# ProcessorTestBoardV1_0.net
KiCad netlist of a schematic drawn in EAGLE
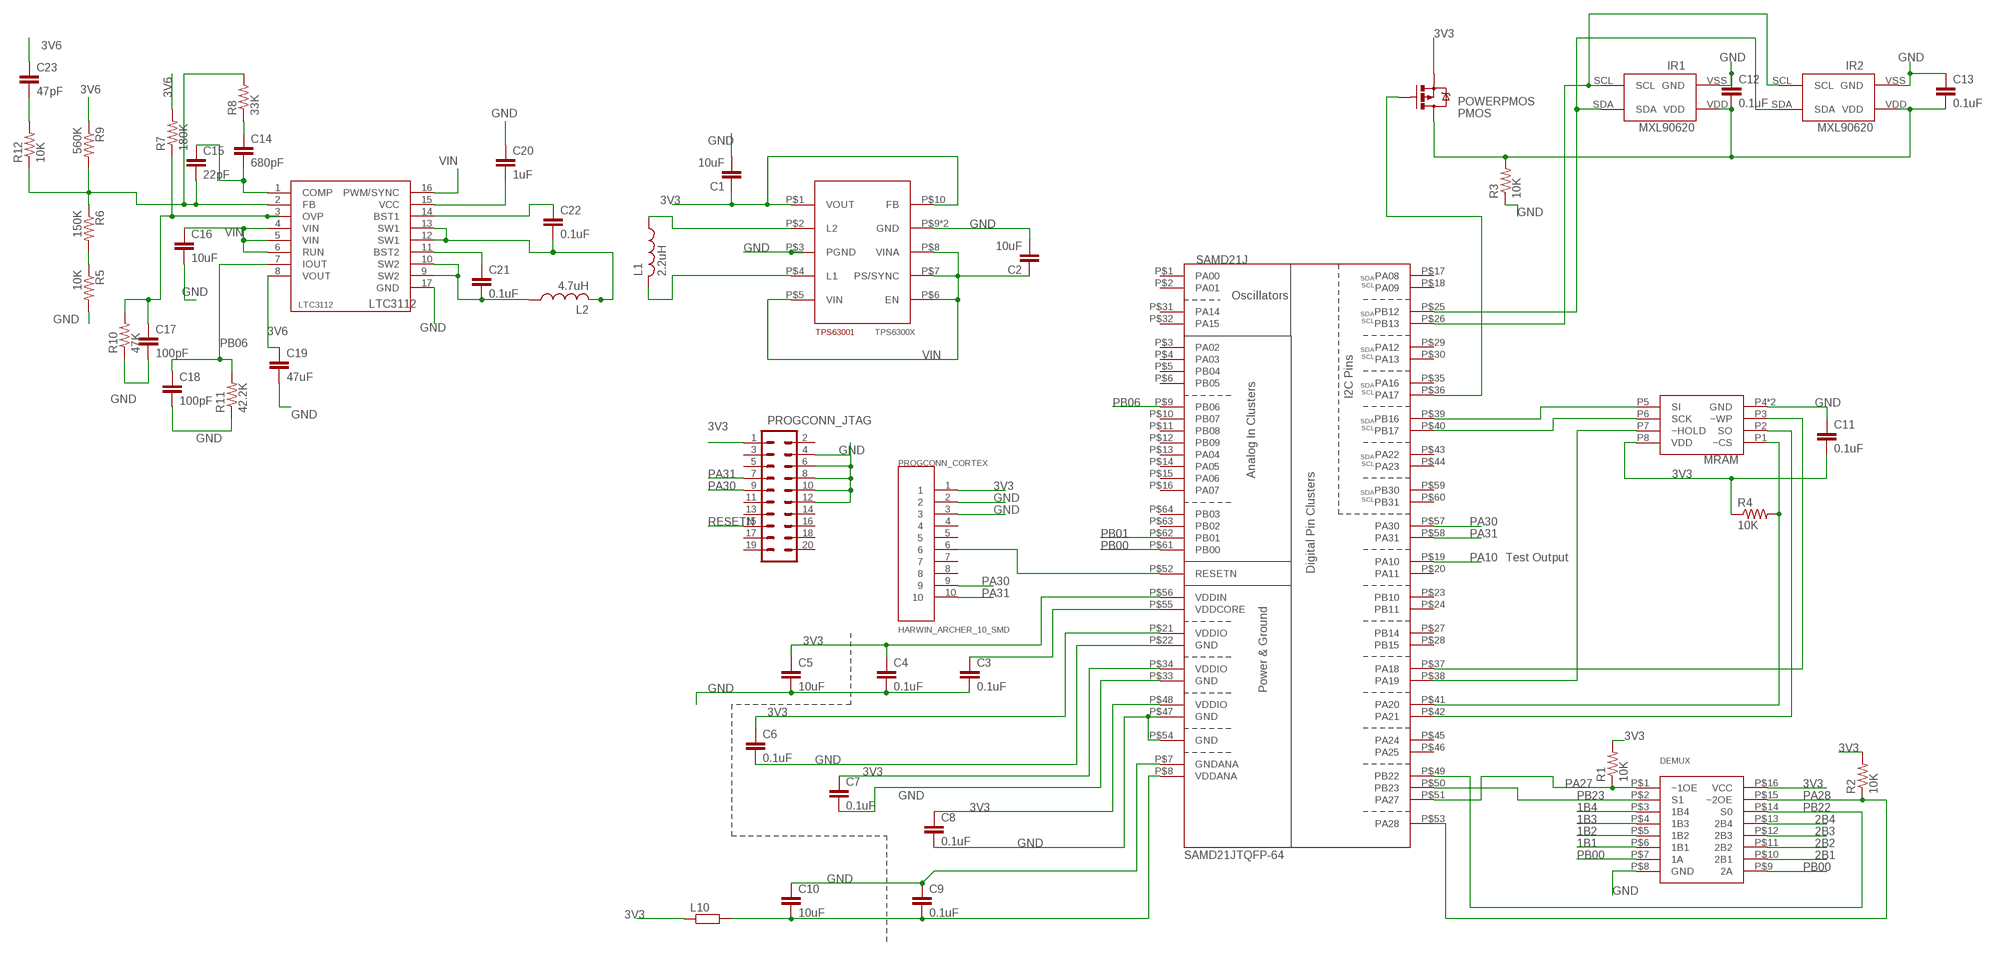
[diagram p0: schematic, sheet 1]

(export (version "E")
  (design (tool "Eeschema 10.0.6"))
  (components
    (comp (ref "C1")
      (value "10uF")
      (footprint "eagle-import:0805")
      (libsource (lib "eagle-import") (part "CAP0805"))
    )
    (comp (ref "C2")
      (value "10uF")
      (footprint "eagle-import:0805")
      (libsource (lib "eagle-import") (part "CAP0805"))
    )
    (comp (ref "C3")
      (value "0.1uF")
      (footprint "eagle-import:0805")
      (libsource (lib "eagle-import") (part "CAP0805"))
    )
    (comp (ref "C4")
      (value "0.1uF")
      (footprint "eagle-import:0805")
      (libsource (lib "eagle-import") (part "CAP0805"))
    )
    (comp (ref "C5")
      (value "10uF")
      (footprint "eagle-import:0805")
      (libsource (lib "eagle-import") (part "CAP0805"))
    )
    (comp (ref "C6")
      (value "0.1uF")
      (footprint "eagle-import:0805")
      (libsource (lib "eagle-import") (part "CAP0805"))
    )
    (comp (ref "C7")
      (value "0.1uF")
      (footprint "eagle-import:0805")
      (libsource (lib "eagle-import") (part "CAP0805"))
    )
    (comp (ref "C8")
      (value "0.1uF")
      (footprint "eagle-import:0805")
      (libsource (lib "eagle-import") (part "CAP0805"))
    )
    (comp (ref "C9")
      (value "0.1uF")
      (footprint "eagle-import:0805")
      (libsource (lib "eagle-import") (part "CAP0805"))
    )
    (comp (ref "C10")
      (value "10uF")
      (footprint "eagle-import:0805")
      (libsource (lib "eagle-import") (part "CAP0805"))
    )
    (comp (ref "C11")
      (value "0.1uF")
      (footprint "eagle-import:0805")
      (libsource (lib "eagle-import") (part "CAP0805"))
    )
    (comp (ref "C12")
      (value "0.1uF")
      (footprint "eagle-import:0805")
      (libsource (lib "eagle-import") (part "CAP0805"))
    )
    (comp (ref "C13")
      (value "0.1uF")
      (footprint "eagle-import:0805")
      (libsource (lib "eagle-import") (part "CAP0805"))
    )
    (comp (ref "C14")
      (value "680pF")
      (footprint "eagle-import:0805")
      (libsource (lib "eagle-import") (part "CAP0805"))
    )
    (comp (ref "C15")
      (value "22pF")
      (footprint "eagle-import:0805")
      (libsource (lib "eagle-import") (part "CAP0805"))
    )
    (comp (ref "C16")
      (value "10uF")
      (footprint "eagle-import:0805")
      (libsource (lib "eagle-import") (part "CAP0805"))
    )
    (comp (ref "C17")
      (value "100pF")
      (footprint "eagle-import:0805")
      (libsource (lib "eagle-import") (part "CAP0805"))
    )
    (comp (ref "C18")
      (value "100pF")
      (footprint "eagle-import:0805")
      (libsource (lib "eagle-import") (part "CAP0805"))
    )
    (comp (ref "C19")
      (value "47uF")
      (footprint "eagle-import:0805")
      (libsource (lib "eagle-import") (part "CAP0805"))
    )
    (comp (ref "C20")
      (value "1uF")
      (footprint "eagle-import:0805")
      (libsource (lib "eagle-import") (part "CAP0805"))
    )
    (comp (ref "C21")
      (value "0.1uF")
      (footprint "eagle-import:0805")
      (libsource (lib "eagle-import") (part "CAP0805"))
    )
    (comp (ref "C22")
      (value "0.1uF")
      (footprint "eagle-import:0805")
      (libsource (lib "eagle-import") (part "CAP0805"))
    )
    (comp (ref "C23")
      (value "47pF")
      (footprint "eagle-import:0805")
      (libsource (lib "eagle-import") (part "CAP0805"))
    )
    (comp (ref "DEMUX")
      (value "SN74CBTLV3253")
      (footprint "eagle-import:SOIC16R")
      (libsource (lib "eagle-import") (part "SN74CBTLV3253"))
    )
    (comp (ref "IR1")
      (value "MXL90620")
      (footprint "eagle-import:MXL90620")
      (libsource (lib "eagle-import") (part "MXL90620"))
    )
    (comp (ref "IR2")
      (value "MXL90620")
      (footprint "eagle-import:MXL90620")
      (libsource (lib "eagle-import") (part "MXL90620"))
    )
    (comp (ref "L1")
      (value "2.2uH")
      (footprint "eagle-import:L3225M")
      (libsource (lib "eagle-import") (part "L-USL3225M"))
    )
    (comp (ref "L2")
      (value "4.7uH")
      (footprint "eagle-import:L3225M")
      (libsource (lib "eagle-import") (part "L-USL3225M"))
    )
    (comp (ref "L10")
      (value "R-EU_R0805")
      (footprint "eagle-import:R0805")
      (libsource (lib "eagle-import") (part "R-EU_R0805"))
    )
    (comp (ref "LTC3112")
      (value "LTC3112")
      (footprint "eagle-import:DHD16")
      (libsource (lib "eagle-import") (part "LTC3112"))
    )
    (comp (ref "MRAM")
      (value "MR25H10CDC")
      (footprint "eagle-import:8PXMO-229")
      (libsource (lib "eagle-import") (part "MR25H10CDC"))
    )
    (comp (ref "PMOS")
      (value "POWERPMOS")
      (footprint "eagle-import:SO08")
      (libsource (lib "eagle-import") (part "POWERPMOS"))
    )
    (comp (ref "PROGCONN_CORTEX")
      (value "HARWIN_ARCHER_10_SMD")
      (footprint "eagle-import:HARWIN_ARCHER_10_SMD")
      (libsource (lib "eagle-import") (part "HARWIN_ARCHER_10_SMD"))
    )
    (comp (ref "PROGCONN_JTAG")
      (value "IDC_JTAG_CONNECTOR")
      (footprint "eagle-import:2X10")
      (libsource (lib "eagle-import") (part "IDC_JTAG_CONNECTOR"))
    )
    (comp (ref "R1")
      (value "10K")
      (footprint "eagle-import:0805")
      (libsource (lib "eagle-import") (part "RESISTOR"))
    )
    (comp (ref "R2")
      (value "10K")
      (footprint "eagle-import:0805")
      (libsource (lib "eagle-import") (part "RESISTOR"))
    )
    (comp (ref "R3")
      (value "10K")
      (footprint "eagle-import:0805")
      (libsource (lib "eagle-import") (part "RESISTOR"))
    )
    (comp (ref "R4")
      (value "10K")
      (footprint "eagle-import:0805")
      (libsource (lib "eagle-import") (part "RESISTOR"))
    )
    (comp (ref "R5")
      (value "10K")
      (footprint "eagle-import:0805")
      (libsource (lib "eagle-import") (part "RESISTOR"))
    )
    (comp (ref "R6")
      (value "150K")
      (footprint "eagle-import:0805")
      (libsource (lib "eagle-import") (part "RESISTOR"))
    )
    (comp (ref "R7")
      (value "180K")
      (footprint "eagle-import:0805")
      (libsource (lib "eagle-import") (part "RESISTOR"))
    )
    (comp (ref "R8")
      (value "33K")
      (footprint "eagle-import:0805")
      (libsource (lib "eagle-import") (part "RESISTOR"))
    )
    (comp (ref "R9")
      (value "560K")
      (footprint "eagle-import:0805")
      (libsource (lib "eagle-import") (part "RESISTOR"))
    )
    (comp (ref "R10")
      (value "47K")
      (footprint "eagle-import:0805")
      (libsource (lib "eagle-import") (part "RESISTOR"))
    )
    (comp (ref "R11")
      (value "42.2K")
      (footprint "eagle-import:0805")
      (libsource (lib "eagle-import") (part "RESISTOR"))
    )
    (comp (ref "R12")
      (value "10K")
      (footprint "eagle-import:0805")
      (libsource (lib "eagle-import") (part "RESISTOR"))
    )
    (comp (ref "SAMD21J")
      (value "SAMD21JTQFP-64")
      (footprint "eagle-import:TQFP-64")
      (libsource (lib "eagle-import") (part "SAMD21JTQFP-64"))
    )
    (comp (ref "TPS63001")
      (value "TPS6300X")
      (footprint "eagle-import:QFN10_POWERPAD")
      (libsource (lib "eagle-import") (part "TPS6300X"))
    )
  )
  (nets
    (net (code "1") (name "/1B1") (class "Default")
      (node (ref "DEMUX") (pin "P$6") (pinfunction "1B1_P$6") (pintype "bidirectional"))
    )
    (net (code "2") (name "/1B2") (class "Default")
      (node (ref "DEMUX") (pin "P$5") (pinfunction "1B2_P$5") (pintype "bidirectional"))
    )
    (net (code "3") (name "/1B3") (class "Default")
      (node (ref "DEMUX") (pin "P$4") (pinfunction "1B3_P$4") (pintype "bidirectional"))
    )
    (net (code "4") (name "/1B4") (class "Default")
      (node (ref "DEMUX") (pin "P$3") (pinfunction "1B4_P$3") (pintype "bidirectional"))
    )
    (net (code "5") (name "/2B1") (class "Default")
      (node (ref "DEMUX") (pin "P$10") (pinfunction "2B1_P$10") (pintype "bidirectional"))
    )
    (net (code "6") (name "/2B2") (class "Default")
      (node (ref "DEMUX") (pin "P$11") (pinfunction "2B2_P$11") (pintype "bidirectional"))
    )
    (net (code "7") (name "/2B3") (class "Default")
      (node (ref "DEMUX") (pin "P$12") (pinfunction "2B3_P$12") (pintype "bidirectional"))
    )
    (net (code "8") (name "/2B4") (class "Default")
      (node (ref "DEMUX") (pin "P$13") (pinfunction "2B4_P$13") (pintype "bidirectional"))
    )
    (net (code "9") (name "/3V3") (class "Default")
      (node (ref "C1") (pin "1") (pinfunction "1_1") (pintype "passive"))
      (node (ref "C11") (pin "2") (pinfunction "2_2") (pintype "passive"))
      (node (ref "C4") (pin "1") (pinfunction "1_1") (pintype "passive"))
      (node (ref "C5") (pin "1") (pinfunction "1_1") (pintype "passive"))
      (node (ref "C6") (pin "1") (pinfunction "1_1") (pintype "passive"))
      (node (ref "C7") (pin "1") (pinfunction "1_1") (pintype "passive"))
      (node (ref "C8") (pin "1") (pinfunction "1_1") (pintype "passive"))
      (node (ref "DEMUX") (pin "P$16") (pinfunction "VCC_P$16") (pintype "bidirectional"))
      (node (ref "L10") (pin "1") (pinfunction "1_1") (pintype "passive"))
      (node (ref "MRAM") (pin "P8") (pinfunction "VDD_P8") (pintype "bidirectional"))
      (node (ref "PMOS") (pin "1") (pinfunction "S_1") (pintype "passive"))
      (node (ref "PMOS") (pin "2") (pinfunction "S_2") (pintype "passive"))
      (node (ref "PMOS") (pin "3") (pinfunction "S_3") (pintype "passive"))
      (node (ref "PROGCONN_CORTEX") (pin "1") (pinfunction "1_1") (pintype "bidirectional"))
      (node (ref "PROGCONN_JTAG") (pin "1") (pinfunction "1_1") (pintype "passive"))
      (node (ref "R1") (pin "2") (pinfunction "2_2") (pintype "passive"))
      (node (ref "R2") (pin "2") (pinfunction "2_2") (pintype "passive"))
      (node (ref "R4") (pin "1") (pinfunction "1_1") (pintype "passive"))
      (node (ref "SAMD21J") (pin "P$21") (pinfunction "VDDIO_P$21") (pintype "power_in"))
      (node (ref "SAMD21J") (pin "P$34") (pinfunction "VDDIO_P$34") (pintype "power_in"))
      (node (ref "SAMD21J") (pin "P$48") (pinfunction "VDDIO_P$48") (pintype "power_in"))
      (node (ref "SAMD21J") (pin "P$56") (pinfunction "VDDIN_P$56") (pintype "power_in"))
      (node (ref "TPS63001") (pin "P$1") (pinfunction "VOUT_P$1") (pintype "output"))
      (node (ref "TPS63001") (pin "P$10") (pinfunction "FB_P$10") (pintype "input"))
    )
    (net (code "10") (name "/3V6") (class "Default")
      (node (ref "C19") (pin "1") (pinfunction "1_1") (pintype "passive"))
      (node (ref "C23") (pin "1") (pinfunction "1_1") (pintype "passive"))
      (node (ref "LTC3112") (pin "8") (pinfunction "VOUT_8") (pintype "bidirectional"))
      (node (ref "R7") (pin "2") (pinfunction "2_2") (pintype "passive"))
      (node (ref "R9") (pin "1") (pinfunction "1_1") (pintype "passive"))
    )
    (net (code "11") (name "/GND") (class "Default")
      (node (ref "C1") (pin "2") (pinfunction "2_2") (pintype "passive"))
      (node (ref "C10") (pin "1") (pinfunction "1_1") (pintype "passive"))
      (node (ref "C11") (pin "1") (pinfunction "1_1") (pintype "passive"))
      (node (ref "C12") (pin "1") (pinfunction "1_1") (pintype "passive"))
      (node (ref "C13") (pin "1") (pinfunction "1_1") (pintype "passive"))
      (node (ref "C16") (pin "2") (pinfunction "2_2") (pintype "passive"))
      (node (ref "C17") (pin "2") (pinfunction "2_2") (pintype "passive"))
      (node (ref "C18") (pin "2") (pinfunction "2_2") (pintype "passive"))
      (node (ref "C19") (pin "2") (pinfunction "2_2") (pintype "passive"))
      (node (ref "C2") (pin "2") (pinfunction "2_2") (pintype "passive"))
      (node (ref "C20") (pin "1") (pinfunction "1_1") (pintype "passive"))
      (node (ref "C3") (pin "2") (pinfunction "2_2") (pintype "passive"))
      (node (ref "C4") (pin "2") (pinfunction "2_2") (pintype "passive"))
      (node (ref "C5") (pin "2") (pinfunction "2_2") (pintype "passive"))
      (node (ref "C6") (pin "2") (pinfunction "2_2") (pintype "passive"))
      (node (ref "C7") (pin "2") (pinfunction "2_2") (pintype "passive"))
      (node (ref "C8") (pin "2") (pinfunction "2_2") (pintype "passive"))
      (node (ref "C9") (pin "1") (pinfunction "1_1") (pintype "passive"))
      (node (ref "DEMUX") (pin "P$8") (pinfunction "GND_P$8") (pintype "bidirectional"))
      (node (ref "IR1") (pin "VSS") (pinfunction "GND_VSS") (pintype "bidirectional"))
      (node (ref "IR2") (pin "VSS") (pinfunction "GND_VSS") (pintype "bidirectional"))
      (node (ref "LTC3112") (pin "17") (pinfunction "GND_17") (pintype "bidirectional"))
      (node (ref "MRAM") (pin "P4") (pinfunction "GND_P4") (pintype "bidirectional"))
      (node (ref "MRAM") (pin "P9") (pinfunction "GND_P9") (pintype "bidirectional"))
      (node (ref "PROGCONN_CORTEX") (pin "2") (pinfunction "2_2") (pintype "bidirectional"))
      (node (ref "PROGCONN_CORTEX") (pin "3") (pinfunction "3_3") (pintype "bidirectional"))
      (node (ref "PROGCONN_JTAG") (pin "10") (pinfunction "10_10") (pintype "passive"))
      (node (ref "PROGCONN_JTAG") (pin "12") (pinfunction "12_12") (pintype "passive"))
      (node (ref "PROGCONN_JTAG") (pin "4") (pinfunction "4_4") (pintype "passive"))
      (node (ref "PROGCONN_JTAG") (pin "6") (pinfunction "6_6") (pintype "passive"))
      (node (ref "PROGCONN_JTAG") (pin "8") (pinfunction "8_8") (pintype "passive"))
      (node (ref "R10") (pin "1") (pinfunction "1_1") (pintype "passive"))
      (node (ref "R11") (pin "1") (pinfunction "1_1") (pintype "passive"))
      (node (ref "R3") (pin "1") (pinfunction "1_1") (pintype "passive"))
      (node (ref "R5") (pin "2") (pinfunction "2_2") (pintype "passive"))
      (node (ref "SAMD21J") (pin "P$22") (pinfunction "GND_P$22") (pintype "power_in"))
      (node (ref "SAMD21J") (pin "P$33") (pinfunction "GND_P$33") (pintype "power_in"))
      (node (ref "SAMD21J") (pin "P$47") (pinfunction "GND_P$47") (pintype "power_in"))
      (node (ref "SAMD21J") (pin "P$54") (pinfunction "GND_P$54") (pintype "power_in"))
      (node (ref "SAMD21J") (pin "P$7") (pinfunction "GNDANA_P$7") (pintype "power_in"))
      (node (ref "TPS63001") (pin "P$3") (pinfunction "PGND_P$3") (pintype "input"))
      (node (ref "TPS63001") (pin "P$9") (pinfunction "GND_P$9") (pintype "input"))
      (node (ref "TPS63001") (pin "PAD") (pinfunction "GND_PAD") (pintype "input"))
    )
    (net (code "12") (name "/PA10") (class "Default")
      (node (ref "SAMD21J") (pin "P$19") (pinfunction "PA10_P$19") (pintype "bidirectional"))
    )
    (net (code "13") (name "/PA27") (class "Default")
      (node (ref "DEMUX") (pin "P$1") (pinfunction "~{1OE}_P$1") (pintype "bidirectional"))
      (node (ref "R1") (pin "1") (pinfunction "1_1") (pintype "passive"))
      (node (ref "SAMD21J") (pin "P$51") (pinfunction "PA27_P$51") (pintype "bidirectional"))
    )
    (net (code "14") (name "/PA28") (class "Default")
      (node (ref "DEMUX") (pin "P$15") (pinfunction "~{2OE}_P$15") (pintype "bidirectional"))
      (node (ref "R2") (pin "1") (pinfunction "1_1") (pintype "passive"))
      (node (ref "SAMD21J") (pin "P$53") (pinfunction "PA28_P$53") (pintype "bidirectional"))
    )
    (net (code "15") (name "/PA30") (class "Default")
      (node (ref "PROGCONN_CORTEX") (pin "9") (pinfunction "9_9") (pintype "bidirectional"))
      (node (ref "PROGCONN_JTAG") (pin "9") (pinfunction "9_9") (pintype "passive"))
      (node (ref "SAMD21J") (pin "P$57") (pinfunction "PA30_P$57") (pintype "bidirectional"))
    )
    (net (code "16") (name "/PA31") (class "Default")
      (node (ref "PROGCONN_CORTEX") (pin "10") (pinfunction "10_10") (pintype "bidirectional"))
      (node (ref "PROGCONN_JTAG") (pin "7") (pinfunction "7_7") (pintype "passive"))
      (node (ref "SAMD21J") (pin "P$58") (pinfunction "PA31_P$58") (pintype "bidirectional"))
    )
    (net (code "17") (name "/PB00") (class "Default")
      (node (ref "DEMUX") (pin "P$7") (pinfunction "1A_P$7") (pintype "bidirectional"))
      (node (ref "DEMUX") (pin "P$9") (pinfunction "2A_P$9") (pintype "bidirectional"))
      (node (ref "SAMD21J") (pin "P$61") (pinfunction "PB00_P$61") (pintype "bidirectional"))
    )
    (net (code "18") (name "/PB01") (class "Default")
      (node (ref "SAMD21J") (pin "P$62") (pinfunction "PB01_P$62") (pintype "bidirectional"))
    )
    (net (code "19") (name "/PB06") (class "Default")
      (node (ref "C18") (pin "1") (pinfunction "1_1") (pintype "passive"))
      (node (ref "LTC3112") (pin "7") (pinfunction "IOUT_7") (pintype "bidirectional"))
      (node (ref "R11") (pin "2") (pinfunction "2_2") (pintype "passive"))
      (node (ref "SAMD21J") (pin "P$9") (pinfunction "PB06_P$9") (pintype "bidirectional"))
    )
    (net (code "20") (name "/PB22") (class "Default")
      (node (ref "DEMUX") (pin "P$14") (pinfunction "S0_P$14") (pintype "bidirectional"))
      (node (ref "SAMD21J") (pin "P$49") (pinfunction "PB22_P$49") (pintype "bidirectional"))
    )
    (net (code "21") (name "/PB23") (class "Default")
      (node (ref "DEMUX") (pin "P$2") (pinfunction "S1_P$2") (pintype "bidirectional"))
      (node (ref "SAMD21J") (pin "P$50") (pinfunction "PB23_P$50") (pintype "bidirectional"))
    )
    (net (code "22") (name "/RESETN") (class "Default")
      (node (ref "PROGCONN_CORTEX") (pin "6") (pinfunction "6_6") (pintype "bidirectional"))
      (node (ref "PROGCONN_JTAG") (pin "15") (pinfunction "15_15") (pintype "passive"))
      (node (ref "SAMD21J") (pin "P$52") (pinfunction "RESETN_P$52") (pintype "input"))
    )
    (net (code "23") (name "/VIN") (class "Default")
      (node (ref "C16") (pin "1") (pinfunction "1_1") (pintype "passive"))
      (node (ref "C2") (pin "1") (pinfunction "1_1") (pintype "passive"))
      (node (ref "LTC3112") (pin "16") (pinfunction "PWM/SYNC_16") (pintype "bidirectional"))
      (node (ref "LTC3112") (pin "4") (pinfunction "VIN_4") (pintype "bidirectional"))
      (node (ref "LTC3112") (pin "5") (pinfunction "VIN_5") (pintype "bidirectional"))
      (node (ref "LTC3112") (pin "6") (pinfunction "RUN_6") (pintype "bidirectional"))
      (node (ref "TPS63001") (pin "P$5") (pinfunction "VIN_P$5") (pintype "input"))
      (node (ref "TPS63001") (pin "P$6") (pinfunction "EN_P$6") (pintype "input"))
      (node (ref "TPS63001") (pin "P$7") (pinfunction "PS/SYNC_P$7") (pintype "input"))
      (node (ref "TPS63001") (pin "P$8") (pinfunction "VINA_P$8") (pintype "input"))
    )
    (net (code "24") (name "Net-(C12-Pad2)") (class "Default")
      (node (ref "C12") (pin "2") (pinfunction "2_2") (pintype "passive"))
      (node (ref "C13") (pin "2") (pinfunction "2_2") (pintype "passive"))
      (node (ref "IR1") (pin "VDD") (pinfunction "VDD_VDD") (pintype "bidirectional"))
      (node (ref "IR2") (pin "VDD") (pinfunction "VDD_VDD") (pintype "bidirectional"))
      (node (ref "PMOS") (pin "5") (pinfunction "D_5") (pintype "passive"))
      (node (ref "PMOS") (pin "6") (pinfunction "D_6") (pintype "passive"))
      (node (ref "PMOS") (pin "7") (pinfunction "D_7") (pintype "passive"))
      (node (ref "PMOS") (pin "8") (pinfunction "D_8") (pintype "passive"))
      (node (ref "R3") (pin "2") (pinfunction "2_2") (pintype "passive"))
    )
    (net (code "25") (name "Net-(C14-Pad1)") (class "Default")
      (node (ref "C14") (pin "1") (pinfunction "1_1") (pintype "passive"))
      (node (ref "R8") (pin "1") (pinfunction "1_1") (pintype "passive"))
    )
    (net (code "26") (name "Net-(C21-Pad2)") (class "Default")
      (node (ref "C21") (pin "2") (pinfunction "2_2") (pintype "passive"))
      (node (ref "L2") (pin "1") (pinfunction "1_1") (pintype "passive"))
      (node (ref "LTC3112") (pin "10") (pinfunction "SW2_10") (pintype "bidirectional"))
      (node (ref "LTC3112") (pin "9") (pinfunction "SW2_9") (pintype "bidirectional"))
    )
    (net (code "27") (name "Net-(C22-Pad2)") (class "Default")
      (node (ref "C22") (pin "2") (pinfunction "2_2") (pintype "passive"))
      (node (ref "L2") (pin "2") (pinfunction "2_2") (pintype "passive"))
      (node (ref "LTC3112") (pin "12") (pinfunction "SW1_12") (pintype "bidirectional"))
      (node (ref "LTC3112") (pin "13") (pinfunction "SW1_13") (pintype "bidirectional"))
    )
    (net (code "28") (name "Net-(C23-Pad2)") (class "Default")
      (node (ref "C23") (pin "2") (pinfunction "2_2") (pintype "passive"))
      (node (ref "R12") (pin "2") (pinfunction "2_2") (pintype "passive"))
    )
    (net (code "29") (name "Net-(LTC3112-BST1)") (class "Default")
      (node (ref "C22") (pin "1") (pinfunction "1_1") (pintype "passive"))
      (node (ref "LTC3112") (pin "14") (pinfunction "BST1_14") (pintype "bidirectional"))
    )
    (net (code "30") (name "Net-(LTC3112-BST2)") (class "Default")
      (node (ref "C21") (pin "1") (pinfunction "1_1") (pintype "passive"))
      (node (ref "LTC3112") (pin "11") (pinfunction "BST2_11") (pintype "bidirectional"))
    )
    (net (code "31") (name "Net-(LTC3112-COMP)") (class "Default")
      (node (ref "C14") (pin "2") (pinfunction "2_2") (pintype "passive"))
      (node (ref "C15") (pin "1") (pinfunction "1_1") (pintype "passive"))
      (node (ref "LTC3112") (pin "1") (pinfunction "COMP_1") (pintype "bidirectional"))
    )
    (net (code "32") (name "Net-(LTC3112-FB)") (class "Default")
      (node (ref "C15") (pin "2") (pinfunction "2_2") (pintype "passive"))
      (node (ref "LTC3112") (pin "2") (pinfunction "FB_2") (pintype "bidirectional"))
      (node (ref "R12") (pin "1") (pinfunction "1_1") (pintype "passive"))
      (node (ref "R6") (pin "1") (pinfunction "1_1") (pintype "passive"))
      (node (ref "R8") (pin "2") (pinfunction "2_2") (pintype "passive"))
      (node (ref "R9") (pin "2") (pinfunction "2_2") (pintype "passive"))
    )
    (net (code "33") (name "Net-(LTC3112-OVP)") (class "Default")
      (node (ref "C17") (pin "1") (pinfunction "1_1") (pintype "passive"))
      (node (ref "LTC3112") (pin "3") (pinfunction "OVP_3") (pintype "bidirectional"))
      (node (ref "R10") (pin "2") (pinfunction "2_2") (pintype "passive"))
      (node (ref "R7") (pin "1") (pinfunction "1_1") (pintype "passive"))
    )
    (net (code "34") (name "Net-(LTC3112-VCC)") (class "Default")
      (node (ref "C20") (pin "2") (pinfunction "2_2") (pintype "passive"))
      (node (ref "LTC3112") (pin "15") (pinfunction "VCC_15") (pintype "bidirectional"))
    )
    (net (code "35") (name "Net-(MRAM-SCK)") (class "Default")
      (node (ref "MRAM") (pin "P6") (pinfunction "SCK_P6") (pintype "bidirectional"))
      (node (ref "SAMD21J") (pin "P$40") (pinfunction "PB17_P$40") (pintype "bidirectional"))
    )
    (net (code "36") (name "Net-(MRAM-SI)") (class "Default")
      (node (ref "MRAM") (pin "P5") (pinfunction "SI_P5") (pintype "bidirectional"))
      (node (ref "SAMD21J") (pin "P$39") (pinfunction "PB16_P$39") (pintype "bidirectional"))
    )
    (net (code "37") (name "Net-(MRAM-SO)") (class "Default")
      (node (ref "MRAM") (pin "P2") (pinfunction "SO_P2") (pintype "bidirectional"))
      (node (ref "SAMD21J") (pin "P$42") (pinfunction "PA21_P$42") (pintype "bidirectional"))
    )
    (net (code "38") (name "Net-(MRAM-~{CS})") (class "Default")
      (node (ref "MRAM") (pin "P1") (pinfunction "~{CS}_P1") (pintype "bidirectional"))
      (node (ref "R4") (pin "2") (pinfunction "2_2") (pintype "passive"))
      (node (ref "SAMD21J") (pin "P$41") (pinfunction "PA20_P$41") (pintype "bidirectional"))
    )
    (net (code "39") (name "Net-(MRAM-~{HOLD})") (class "Default")
      (node (ref "MRAM") (pin "P7") (pinfunction "~{HOLD}_P7") (pintype "bidirectional"))
      (node (ref "SAMD21J") (pin "P$38") (pinfunction "PA19_P$38") (pintype "bidirectional"))
    )
    (net (code "40") (name "Net-(MRAM-~{WP})") (class "Default")
      (node (ref "MRAM") (pin "P3") (pinfunction "~{WP}_P3") (pintype "bidirectional"))
      (node (ref "SAMD21J") (pin "P$37") (pinfunction "PA18_P$37") (pintype "bidirectional"))
    )
    (net (code "41") (name "Net-(PMOS-G)") (class "Default")
      (node (ref "PMOS") (pin "4") (pinfunction "G_4") (pintype "passive"))
      (node (ref "SAMD21J") (pin "P$36") (pinfunction "PA17_P$36") (pintype "bidirectional"))
    )
    (net (code "42") (name "Net-(R5-Pad1)") (class "Default")
      (node (ref "R5") (pin "1") (pinfunction "1_1") (pintype "passive"))
      (node (ref "R6") (pin "2") (pinfunction "2_2") (pintype "passive"))
    )
    (net (code "43") (name "Net-(SAMD21J-PB12)") (class "Default")
      (node (ref "IR1") (pin "SDA") (pinfunction "SDA_SDA") (pintype "bidirectional"))
      (node (ref "IR2") (pin "SDA") (pinfunction "SDA_SDA") (pintype "bidirectional"))
      (node (ref "SAMD21J") (pin "P$25") (pinfunction "PB12_P$25") (pintype "bidirectional"))
    )
    (net (code "44") (name "Net-(SAMD21J-PB13)") (class "Default")
      (node (ref "IR1") (pin "SCL") (pinfunction "SCL_SCL") (pintype "bidirectional"))
      (node (ref "IR2") (pin "SCL") (pinfunction "SCL_SCL") (pintype "bidirectional"))
      (node (ref "SAMD21J") (pin "P$26") (pinfunction "PB13_P$26") (pintype "bidirectional"))
    )
    (net (code "45") (name "Net-(SAMD21J-VDDANA)") (class "Default")
      (node (ref "C10") (pin "2") (pinfunction "2_2") (pintype "passive"))
      (node (ref "C9") (pin "2") (pinfunction "2_2") (pintype "passive"))
      (node (ref "L10") (pin "2") (pinfunction "2_2") (pintype "passive"))
      (node (ref "SAMD21J") (pin "P$8") (pinfunction "VDDANA_P$8") (pintype "power_in"))
    )
    (net (code "46") (name "Net-(SAMD21J-VDDCORE)") (class "Default")
      (node (ref "C3") (pin "1") (pinfunction "1_1") (pintype "passive"))
      (node (ref "SAMD21J") (pin "P$55") (pinfunction "VDDCORE_P$55") (pintype "power_in"))
    )
    (net (code "47") (name "Net-(TPS63001-L1)") (class "Default")
      (node (ref "L1") (pin "2") (pinfunction "2_2") (pintype "passive"))
      (node (ref "TPS63001") (pin "P$4") (pinfunction "L1_P$4") (pintype "input"))
    )
    (net (code "48") (name "Net-(TPS63001-L2)") (class "Default")
      (node (ref "L1") (pin "1") (pinfunction "1_1") (pintype "passive"))
      (node (ref "TPS63001") (pin "P$2") (pinfunction "L2_P$2") (pintype "input"))
    )
    (net (code "49") (name "unconnected-(PROGCONN_CORTEX-Pad4)") (class "Default")
      (node (ref "PROGCONN_CORTEX") (pin "4") (pinfunction "4_4") (pintype "bidirectional"))
    )
    (net (code "50") (name "unconnected-(PROGCONN_CORTEX-Pad5)") (class "Default")
      (node (ref "PROGCONN_CORTEX") (pin "5") (pinfunction "5_5") (pintype "bidirectional"))
    )
    (net (code "51") (name "unconnected-(PROGCONN_CORTEX-Pad7)") (class "Default")
      (node (ref "PROGCONN_CORTEX") (pin "7") (pinfunction "7_7") (pintype "bidirectional"))
    )
    (net (code "52") (name "unconnected-(PROGCONN_CORTEX-Pad8)") (class "Default")
      (node (ref "PROGCONN_CORTEX") (pin "8") (pinfunction "8_8") (pintype "bidirectional"))
    )
    (net (code "53") (name "unconnected-(PROGCONN_JTAG-Pad2)") (class "Default")
      (node (ref "PROGCONN_JTAG") (pin "2") (pinfunction "2_2") (pintype "passive"))
    )
    (net (code "54") (name "unconnected-(PROGCONN_JTAG-Pad3)") (class "Default")
      (node (ref "PROGCONN_JTAG") (pin "3") (pinfunction "3_3") (pintype "passive"))
    )
    (net (code "55") (name "unconnected-(PROGCONN_JTAG-Pad5)") (class "Default")
      (node (ref "PROGCONN_JTAG") (pin "5") (pinfunction "5_5") (pintype "passive"))
    )
    (net (code "56") (name "unconnected-(PROGCONN_JTAG-Pad11)") (class "Default")
      (node (ref "PROGCONN_JTAG") (pin "11") (pinfunction "11_11") (pintype "passive"))
    )
    (net (code "57") (name "unconnected-(PROGCONN_JTAG-Pad13)") (class "Default")
      (node (ref "PROGCONN_JTAG") (pin "13") (pinfunction "13_13") (pintype "passive"))
    )
    (net (code "58") (name "unconnected-(PROGCONN_JTAG-Pad14)") (class "Default")
      (node (ref "PROGCONN_JTAG") (pin "14") (pinfunction "14_14") (pintype "passive"))
    )
    (net (code "59") (name "unconnected-(PROGCONN_JTAG-Pad16)") (class "Default")
      (node (ref "PROGCONN_JTAG") (pin "16") (pinfunction "16_16") (pintype "passive"))
    )
    (net (code "60") (name "unconnected-(PROGCONN_JTAG-Pad17)") (class "Default")
      (node (ref "PROGCONN_JTAG") (pin "17") (pinfunction "17_17") (pintype "passive"))
    )
    (net (code "61") (name "unconnected-(PROGCONN_JTAG-Pad18)") (class "Default")
      (node (ref "PROGCONN_JTAG") (pin "18") (pinfunction "18_18") (pintype "passive"))
    )
    (net (code "62") (name "unconnected-(PROGCONN_JTAG-Pad19)") (class "Default")
      (node (ref "PROGCONN_JTAG") (pin "19") (pinfunction "19_19") (pintype "passive"))
    )
    (net (code "63") (name "unconnected-(PROGCONN_JTAG-Pad20)") (class "Default")
      (node (ref "PROGCONN_JTAG") (pin "20") (pinfunction "20_20") (pintype "passive"))
    )
    (net (code "64") (name "unconnected-(SAMD21J-PA00-PadP$1)") (class "Default")
      (node (ref "SAMD21J") (pin "P$1") (pinfunction "PA00_P$1") (pintype "bidirectional"))
    )
    (net (code "65") (name "unconnected-(SAMD21J-PA01-PadP$2)") (class "Default")
      (node (ref "SAMD21J") (pin "P$2") (pinfunction "PA01_P$2") (pintype "bidirectional"))
    )
    (net (code "66") (name "unconnected-(SAMD21J-PA02-PadP$3)") (class "Default")
      (node (ref "SAMD21J") (pin "P$3") (pinfunction "PA02_P$3") (pintype "bidirectional"))
    )
    (net (code "67") (name "unconnected-(SAMD21J-PA03-PadP$4)") (class "Default")
      (node (ref "SAMD21J") (pin "P$4") (pinfunction "PA03_P$4") (pintype "bidirectional"))
    )
    (net (code "68") (name "unconnected-(SAMD21J-PA04-PadP$13)") (class "Default")
      (node (ref "SAMD21J") (pin "P$13") (pinfunction "PA04_P$13") (pintype "bidirectional"))
    )
    (net (code "69") (name "unconnected-(SAMD21J-PA05-PadP$14)") (class "Default")
      (node (ref "SAMD21J") (pin "P$14") (pinfunction "PA05_P$14") (pintype "bidirectional"))
    )
    (net (code "70") (name "unconnected-(SAMD21J-PA06-PadP$15)") (class "Default")
      (node (ref "SAMD21J") (pin "P$15") (pinfunction "PA06_P$15") (pintype "bidirectional"))
    )
    (net (code "71") (name "unconnected-(SAMD21J-PA07-PadP$16)") (class "Default")
      (node (ref "SAMD21J") (pin "P$16") (pinfunction "PA07_P$16") (pintype "bidirectional"))
    )
    (net (code "72") (name "unconnected-(SAMD21J-PA08-PadP$17)") (class "Default")
      (node (ref "SAMD21J") (pin "P$17") (pinfunction "PA08_P$17") (pintype "bidirectional"))
    )
    (net (code "73") (name "unconnected-(SAMD21J-PA09-PadP$18)") (class "Default")
      (node (ref "SAMD21J") (pin "P$18") (pinfunction "PA09_P$18") (pintype "bidirectional"))
    )
    (net (code "74") (name "unconnected-(SAMD21J-PA11-PadP$20)") (class "Default")
      (node (ref "SAMD21J") (pin "P$20") (pinfunction "PA11_P$20") (pintype "bidirectional"))
    )
    (net (code "75") (name "unconnected-(SAMD21J-PA12-PadP$29)") (class "Default")
      (node (ref "SAMD21J") (pin "P$29") (pinfunction "PA12_P$29") (pintype "bidirectional"))
    )
    (net (code "76") (name "unconnected-(SAMD21J-PA13-PadP$30)") (class "Default")
      (node (ref "SAMD21J") (pin "P$30") (pinfunction "PA13_P$30") (pintype "bidirectional"))
    )
    (net (code "77") (name "unconnected-(SAMD21J-PA14-PadP$31)") (class "Default")
      (node (ref "SAMD21J") (pin "P$31") (pinfunction "PA14_P$31") (pintype "bidirectional"))
    )
    (net (code "78") (name "unconnected-(SAMD21J-PA15-PadP$32)") (class "Default")
      (node (ref "SAMD21J") (pin "P$32") (pinfunction "PA15_P$32") (pintype "bidirectional"))
    )
    (net (code "79") (name "unconnected-(SAMD21J-PA16-PadP$35)") (class "Default")
      (node (ref "SAMD21J") (pin "P$35") (pinfunction "PA16_P$35") (pintype "bidirectional"))
    )
    (net (code "80") (name "unconnected-(SAMD21J-PA22-PadP$43)") (class "Default")
      (node (ref "SAMD21J") (pin "P$43") (pinfunction "PA22_P$43") (pintype "bidirectional"))
    )
    (net (code "81") (name "unconnected-(SAMD21J-PA23-PadP$44)") (class "Default")
      (node (ref "SAMD21J") (pin "P$44") (pinfunction "PA23_P$44") (pintype "bidirectional"))
    )
    (net (code "82") (name "unconnected-(SAMD21J-PA24-PadP$45)") (class "Default")
      (node (ref "SAMD21J") (pin "P$45") (pinfunction "PA24_P$45") (pintype "bidirectional"))
    )
    (net (code "83") (name "unconnected-(SAMD21J-PA25-PadP$46)") (class "Default")
      (node (ref "SAMD21J") (pin "P$46") (pinfunction "PA25_P$46") (pintype "bidirectional"))
    )
    (net (code "84") (name "unconnected-(SAMD21J-PB02-PadP$63)") (class "Default")
      (node (ref "SAMD21J") (pin "P$63") (pinfunction "PB02_P$63") (pintype "bidirectional"))
    )
    (net (code "85") (name "unconnected-(SAMD21J-PB03-PadP$64)") (class "Default")
      (node (ref "SAMD21J") (pin "P$64") (pinfunction "PB03_P$64") (pintype "bidirectional"))
    )
    (net (code "86") (name "unconnected-(SAMD21J-PB04-PadP$5)") (class "Default")
      (node (ref "SAMD21J") (pin "P$5") (pinfunction "PB04_P$5") (pintype "bidirectional"))
    )
    (net (code "87") (name "unconnected-(SAMD21J-PB05-PadP$6)") (class "Default")
      (node (ref "SAMD21J") (pin "P$6") (pinfunction "PB05_P$6") (pintype "bidirectional"))
    )
    (net (code "88") (name "unconnected-(SAMD21J-PB07-PadP$10)") (class "Default")
      (node (ref "SAMD21J") (pin "P$10") (pinfunction "PB07_P$10") (pintype "bidirectional"))
    )
    (net (code "89") (name "unconnected-(SAMD21J-PB08-PadP$11)") (class "Default")
      (node (ref "SAMD21J") (pin "P$11") (pinfunction "PB08_P$11") (pintype "bidirectional"))
    )
    (net (code "90") (name "unconnected-(SAMD21J-PB09-PadP$12)") (class "Default")
      (node (ref "SAMD21J") (pin "P$12") (pinfunction "PB09_P$12") (pintype "bidirectional"))
    )
    (net (code "91") (name "unconnected-(SAMD21J-PB10-PadP$23)") (class "Default")
      (node (ref "SAMD21J") (pin "P$23") (pinfunction "PB10_P$23") (pintype "bidirectional"))
    )
    (net (code "92") (name "unconnected-(SAMD21J-PB11-PadP$24)") (class "Default")
      (node (ref "SAMD21J") (pin "P$24") (pinfunction "PB11_P$24") (pintype "bidirectional"))
    )
    (net (code "93") (name "unconnected-(SAMD21J-PB14-PadP$27)") (class "Default")
      (node (ref "SAMD21J") (pin "P$27") (pinfunction "PB14_P$27") (pintype "bidirectional"))
    )
    (net (code "94") (name "unconnected-(SAMD21J-PB15-PadP$28)") (class "Default")
      (node (ref "SAMD21J") (pin "P$28") (pinfunction "PB15_P$28") (pintype "bidirectional"))
    )
    (net (code "95") (name "unconnected-(SAMD21J-PB30-PadP$59)") (class "Default")
      (node (ref "SAMD21J") (pin "P$59") (pinfunction "PB30_P$59") (pintype "bidirectional"))
    )
    (net (code "96") (name "unconnected-(SAMD21J-PB31-PadP$60)") (class "Default")
      (node (ref "SAMD21J") (pin "P$60") (pinfunction "PB31_P$60") (pintype "bidirectional"))
    )
  )
)
